# at32f415_soc.net
KiCad netlist of a schematic drawn in Altium Designer
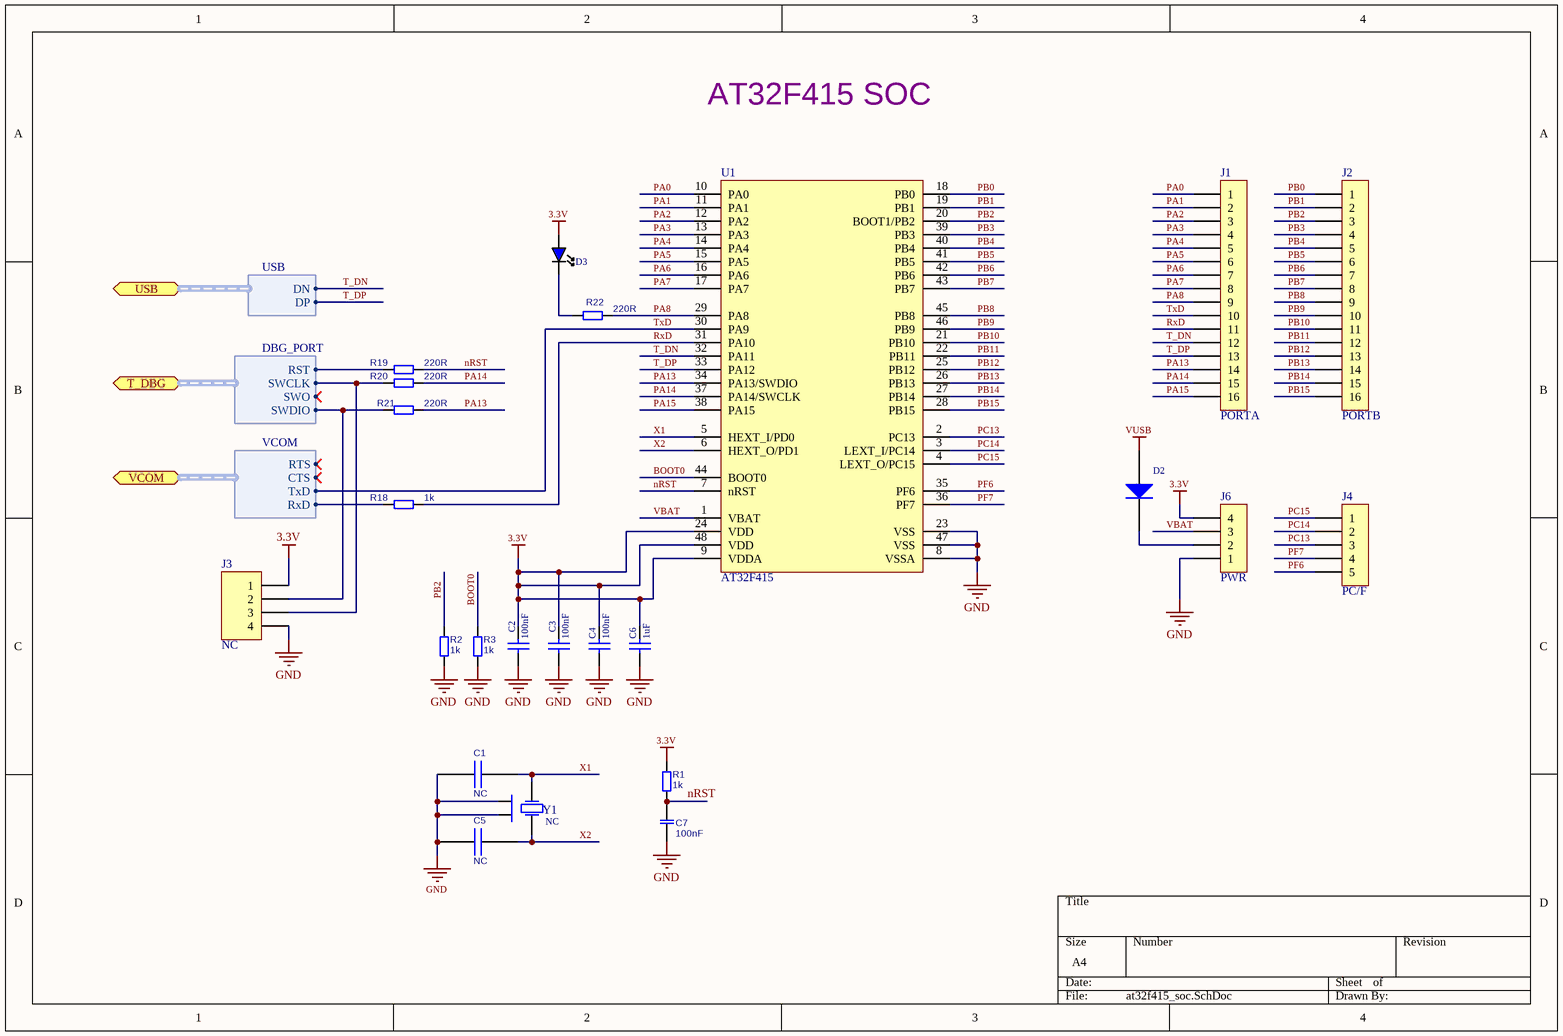
[diagram p0: at32f415_soc.SchDoc]

(export (version "E")
  (design (tool "Eeschema 10.0.6"))
  (components
    (comp (ref "C1")
      (value "NC")
      (footprint "C0402")
      (description "Ceramic Capacitor")
      (libsource (lib "hdesign") (part "Cap1"))
    )
    (comp (ref "C2")
      (value "100nF")
      (footprint "C0402")
      (description "Capacitor")
      (fields (field (name "PUBLISHER") "Altium Limited"))
      (libsource (lib "Miscellaneous Devices") (part "Cap"))
    )
    (comp (ref "C3")
      (value "100nF")
      (footprint "C0402")
      (description "Capacitor")
      (fields (field (name "PUBLISHER") "Altium Limited"))
      (libsource (lib "Miscellaneous Devices") (part "Cap"))
    )
    (comp (ref "C4")
      (value "100nF")
      (footprint "C0402")
      (description "Capacitor")
      (fields (field (name "PUBLISHER") "Altium Limited"))
      (libsource (lib "Miscellaneous Devices") (part "Cap"))
    )
    (comp (ref "C5")
      (value "NC")
      (footprint "C0402")
      (description "Ceramic Capacitor")
      (libsource (lib "hdesign") (part "Cap1"))
    )
    (comp (ref "C6")
      (value "1uF")
      (footprint "C0603")
      (description "Capacitor")
      (fields (field (name "PUBLISHER") "Altium Limited"))
      (libsource (lib "Miscellaneous Devices") (part "Cap"))
    )
    (comp (ref "C7")
      (value "100nF")
      (footprint "C0402")
      (description "Ceramic Capacitor")
      (libsource (lib "hdesign") (part "Cap"))
    )
    (comp (ref "D2")
      (value "Diode")
      (footprint "SOD123")
      (description "Generic Diode")
      (libsource (lib "hdesign") (part "Diode"))
    )
    (comp (ref "D3")
      (value "User LED")
      (footprint "LED0603")
      (description "Green LED")
      (fields (field (name "PART NUMBER") "150060VS75020"))
      (libsource (lib "hdesign") (part "LED_BLUE"))
    )
    (comp (ref "J1")
      (value "PORTA")
      (footprint "HDR1X16")
      (description "100mil, 1x16 header")
      (libsource (lib "at32f415") (part "HEADER1x16"))
    )
    (comp (ref "J2")
      (value "PORTB")
      (footprint "HDR1X16")
      (description "100mil, 1x16 header")
      (libsource (lib "at32f415") (part "HEADER1x16"))
    )
    (comp (ref "J3")
      (value "NC")
      (footprint "HDR1X4")
      (description "Header, 4-Pin")
      (libsource (lib "Miscellaneous Connectors") (part "Header 4"))
    )
    (comp (ref "J4")
      (value "PC/F")
      (footprint "HDR1X5")
      (description "100mil, 1x5 header")
      (libsource (lib "at32f415") (part "HEADER1X5"))
    )
    (comp (ref "J6")
      (value "PWR")
      (footprint "HDR1X4")
      (description "100mil, 1x4 header")
      (libsource (lib "at32f415") (part "HEADER1X4"))
    )
    (comp (ref "R1")
      (value "1k")
      (footprint "R0402")
      (description "Resistor")
      (libsource (lib "hdesign") (part "Res"))
    )
    (comp (ref "R2")
      (value "1k")
      (footprint "R0402")
      (description "Resistor")
      (libsource (lib "hdesign") (part "Res"))
    )
    (comp (ref "R3")
      (value "1k")
      (footprint "R0402")
      (description "Resistor")
      (libsource (lib "hdesign") (part "Res"))
    )
    (comp (ref "R18")
      (value "1k")
      (footprint "R0402")
      (description "Resistor")
      (libsource (lib "hdesign") (part "Res"))
    )
    (comp (ref "R19")
      (value "220R")
      (footprint "R0402")
      (description "Resistor")
      (libsource (lib "hdesign") (part "Res"))
    )
    (comp (ref "R20")
      (value "220R")
      (footprint "R0402")
      (description "Resistor")
      (libsource (lib "hdesign") (part "Res"))
    )
    (comp (ref "R21")
      (value "220R")
      (footprint "R0402")
      (description "Resistor")
      (libsource (lib "hdesign") (part "Res"))
    )
    (comp (ref "R22")
      (value "220R")
      (footprint "R0402")
      (description "Resistor")
      (libsource (lib "hdesign") (part "Res"))
    )
    (comp (ref "U1")
      (value "AT32F415")
      (footprint "LQFP48_M")
      (description "Cortex-M4 MCU")
      (libsource (lib "at32f415") (part "AT32F415"))
    )
    (comp (ref "Y1")
      (value "NC")
      (footprint "XTAL_3225")
      (description "12Mhz CERAMIC SMD CRYSTAL")
      (libsource (lib "hdesign") (part "XTAL_4_PIN"))
    )
  )
  (nets
    (net (code "4") (name "/BOOT0") (class "Default")
      (node (ref "R3") (pin "1") (pinfunction "K_1") (pintype "passive"))
      (node (ref "U1") (pin "44") (pinfunction "BOOT0_44") (pintype "passive"))
    )
    (net (code "5") (name "/PA0") (class "Default")
      (node (ref "J1") (pin "1") (pinfunction "1_1") (pintype "passive"))
      (node (ref "U1") (pin "10") (pinfunction "PA0_10") (pintype "passive"))
    )
    (net (code "6") (name "/PA1") (class "Default")
      (node (ref "J1") (pin "2") (pinfunction "2_2") (pintype "passive"))
      (node (ref "U1") (pin "11") (pinfunction "PA1_11") (pintype "passive"))
    )
    (net (code "7") (name "/PA2") (class "Default")
      (node (ref "J1") (pin "3") (pinfunction "3_3") (pintype "passive"))
      (node (ref "U1") (pin "12") (pinfunction "PA2_12") (pintype "passive"))
    )
    (net (code "8") (name "/PA3") (class "Default")
      (node (ref "J1") (pin "4") (pinfunction "4_4") (pintype "passive"))
      (node (ref "U1") (pin "13") (pinfunction "PA3_13") (pintype "passive"))
    )
    (net (code "9") (name "/PA4") (class "Default")
      (node (ref "J1") (pin "5") (pinfunction "5_5") (pintype "passive"))
      (node (ref "U1") (pin "14") (pinfunction "PA4_14") (pintype "passive"))
    )
    (net (code "10") (name "/PA5") (class "Default")
      (node (ref "J1") (pin "6") (pinfunction "6_6") (pintype "passive"))
      (node (ref "U1") (pin "15") (pinfunction "PA5_15") (pintype "passive"))
    )
    (net (code "11") (name "/PA6") (class "Default")
      (node (ref "J1") (pin "7") (pinfunction "7_7") (pintype "passive"))
      (node (ref "U1") (pin "16") (pinfunction "PA6_16") (pintype "passive"))
    )
    (net (code "12") (name "/PA7") (class "Default")
      (node (ref "J1") (pin "8") (pinfunction "8_8") (pintype "passive"))
      (node (ref "U1") (pin "17") (pinfunction "PA7_17") (pintype "passive"))
    )
    (net (code "13") (name "/PA8") (class "Default")
      (node (ref "J1") (pin "9") (pinfunction "9_9") (pintype "passive"))
      (node (ref "R22") (pin "1") (pinfunction "K_1") (pintype "passive"))
      (node (ref "U1") (pin "29") (pinfunction "PA8_29") (pintype "passive"))
    )
    (net (code "14") (name "/PA13") (class "Default")
      (node (ref "J1") (pin "14") (pinfunction "14_14") (pintype "passive"))
      (node (ref "R21") (pin "1") (pinfunction "K_1") (pintype "passive"))
      (node (ref "U1") (pin "34") (pinfunction "PA13/SWDIO_34") (pintype "passive"))
    )
    (net (code "15") (name "/PA14") (class "Default")
      (node (ref "J1") (pin "15") (pinfunction "15_15") (pintype "passive"))
      (node (ref "R20") (pin "1") (pinfunction "K_1") (pintype "passive"))
      (node (ref "U1") (pin "37") (pinfunction "PA14/SWCLK_37") (pintype "passive"))
    )
    (net (code "16") (name "/PA15") (class "Default")
      (node (ref "J1") (pin "16") (pinfunction "16_16") (pintype "passive"))
      (node (ref "U1") (pin "38") (pinfunction "PA15_38") (pintype "passive"))
    )
    (net (code "17") (name "/PB0") (class "Default")
      (node (ref "J2") (pin "1") (pinfunction "1_1") (pintype "passive"))
      (node (ref "U1") (pin "18") (pinfunction "PB0_18") (pintype "passive"))
    )
    (net (code "18") (name "/PB1") (class "Default")
      (node (ref "J2") (pin "2") (pinfunction "2_2") (pintype "passive"))
      (node (ref "U1") (pin "19") (pinfunction "PB1_19") (pintype "passive"))
    )
    (net (code "19") (name "/PB2") (class "Default")
      (node (ref "J2") (pin "3") (pinfunction "3_3") (pintype "passive"))
      (node (ref "R2") (pin "2") (pinfunction "A_2") (pintype "passive"))
      (node (ref "U1") (pin "20") (pinfunction "BOOT1/PB2_20") (pintype "passive"))
    )
    (net (code "20") (name "/PB3") (class "Default")
      (node (ref "J2") (pin "4") (pinfunction "4_4") (pintype "passive"))
      (node (ref "U1") (pin "39") (pinfunction "PB3_39") (pintype "passive"))
    )
    (net (code "21") (name "/PB4") (class "Default")
      (node (ref "J2") (pin "5") (pinfunction "5_5") (pintype "passive"))
      (node (ref "U1") (pin "40") (pinfunction "PB4_40") (pintype "passive"))
    )
    (net (code "22") (name "/PB5") (class "Default")
      (node (ref "J2") (pin "6") (pinfunction "6_6") (pintype "passive"))
      (node (ref "U1") (pin "41") (pinfunction "PB5_41") (pintype "passive"))
    )
    (net (code "23") (name "/PB6") (class "Default")
      (node (ref "J2") (pin "7") (pinfunction "7_7") (pintype "passive"))
      (node (ref "U1") (pin "42") (pinfunction "PB6_42") (pintype "passive"))
    )
    (net (code "24") (name "/PB7") (class "Default")
      (node (ref "J2") (pin "8") (pinfunction "8_8") (pintype "passive"))
      (node (ref "U1") (pin "43") (pinfunction "PB7_43") (pintype "passive"))
    )
    (net (code "25") (name "/PB8") (class "Default")
      (node (ref "J2") (pin "9") (pinfunction "9_9") (pintype "passive"))
      (node (ref "U1") (pin "45") (pinfunction "PB8_45") (pintype "passive"))
    )
    (net (code "26") (name "/PB9") (class "Default")
      (node (ref "J2") (pin "10") (pinfunction "10_10") (pintype "passive"))
      (node (ref "U1") (pin "46") (pinfunction "PB9_46") (pintype "passive"))
    )
    (net (code "27") (name "/PB10") (class "Default")
      (node (ref "J2") (pin "11") (pinfunction "11_11") (pintype "passive"))
      (node (ref "U1") (pin "21") (pinfunction "PB10_21") (pintype "passive"))
    )
    (net (code "28") (name "/PB11") (class "Default")
      (node (ref "J2") (pin "12") (pinfunction "12_12") (pintype "passive"))
      (node (ref "U1") (pin "22") (pinfunction "PB11_22") (pintype "passive"))
    )
    (net (code "29") (name "/PB12") (class "Default")
      (node (ref "J2") (pin "13") (pinfunction "13_13") (pintype "passive"))
      (node (ref "U1") (pin "25") (pinfunction "PB12_25") (pintype "passive"))
    )
    (net (code "30") (name "/PB13") (class "Default")
      (node (ref "J2") (pin "14") (pinfunction "14_14") (pintype "passive"))
      (node (ref "U1") (pin "26") (pinfunction "PB13_26") (pintype "passive"))
    )
    (net (code "31") (name "/PB14") (class "Default")
      (node (ref "J2") (pin "15") (pinfunction "15_15") (pintype "passive"))
      (node (ref "U1") (pin "27") (pinfunction "PB14_27") (pintype "passive"))
    )
    (net (code "32") (name "/PB15") (class "Default")
      (node (ref "J2") (pin "16") (pinfunction "16_16") (pintype "passive"))
      (node (ref "U1") (pin "28") (pinfunction "PB15_28") (pintype "passive"))
    )
    (net (code "33") (name "/PC13") (class "Default")
      (node (ref "J4") (pin "3") (pinfunction "3_3") (pintype "passive"))
      (node (ref "U1") (pin "2") (pinfunction "PC13_2") (pintype "passive"))
    )
    (net (code "34") (name "/PC14") (class "Default")
      (node (ref "J4") (pin "2") (pinfunction "2_2") (pintype "passive"))
      (node (ref "U1") (pin "3") (pinfunction "LEXT_I/PC14_3") (pintype "passive"))
    )
    (net (code "35") (name "/PC15") (class "Default")
      (node (ref "J4") (pin "1") (pinfunction "1_1") (pintype "passive"))
      (node (ref "U1") (pin "4") (pinfunction "LEXT_O/PC15_4") (pintype "passive"))
    )
    (net (code "36") (name "/PF6") (class "Default")
      (node (ref "J4") (pin "5") (pinfunction "5_5") (pintype "passive"))
      (node (ref "U1") (pin "35") (pinfunction "PF6_35") (pintype "passive"))
    )
    (net (code "37") (name "/PF7") (class "Default")
      (node (ref "J4") (pin "4") (pinfunction "4_4") (pintype "passive"))
      (node (ref "U1") (pin "36") (pinfunction "PF7_36") (pintype "passive"))
    )
    (net (code "38") (name "/RST") (class "Default")
      (node (ref "R19") (pin "2") (pinfunction "A_2") (pintype "passive"))
    )
    (net (code "39") (name "/RxD") (class "Default")
      (node (ref "J1") (pin "11") (pinfunction "11_11") (pintype "passive"))
      (node (ref "R18") (pin "2") (pinfunction "A_2") (pintype "passive"))
      (node (ref "U1") (pin "31") (pinfunction "PA10_31") (pintype "passive"))
    )
    (net (code "40") (name "/SWCLK") (class "Default")
      (node (ref "J3") (pin "3") (pinfunction "3_3") (pintype "passive"))
      (node (ref "R20") (pin "2") (pinfunction "A_2") (pintype "passive"))
    )
    (net (code "41") (name "/SWDIO") (class "Default")
      (node (ref "J3") (pin "2") (pinfunction "2_2") (pintype "passive"))
      (node (ref "R21") (pin "2") (pinfunction "A_2") (pintype "passive"))
    )
    (net (code "42") (name "/T_DN") (class "Default")
      (node (ref "J1") (pin "12") (pinfunction "12_12") (pintype "passive"))
      (node (ref "U1") (pin "32") (pinfunction "PA11_32") (pintype "passive"))
    )
    (net (code "43") (name "/T_DP") (class "Default")
      (node (ref "J1") (pin "13") (pinfunction "13_13") (pintype "passive"))
      (node (ref "U1") (pin "33") (pinfunction "PA12_33") (pintype "passive"))
    )
    (net (code "44") (name "/TxD") (class "Default")
      (node (ref "J1") (pin "10") (pinfunction "10_10") (pintype "passive"))
      (node (ref "U1") (pin "30") (pinfunction "PA9_30") (pintype "passive"))
    )
    (net (code "45") (name "/VBAT") (class "Default")
      (node (ref "J6") (pin "3") (pinfunction "3_3") (pintype "passive"))
      (node (ref "U1") (pin "1") (pinfunction "VBAT_1") (pintype "passive"))
    )
    (net (code "46") (name "/X1") (class "Default")
      (node (ref "C1") (pin "2") (pinfunction "N_2") (pintype "passive"))
      (node (ref "U1") (pin "5") (pinfunction "HEXT_I/PD0_5") (pintype "passive"))
      (node (ref "Y1") (pin "1") (pinfunction "X1_1") (pintype "passive"))
    )
    (net (code "47") (name "/X2") (class "Default")
      (node (ref "C5") (pin "2") (pinfunction "N_2") (pintype "passive"))
      (node (ref "U1") (pin "6") (pinfunction "HEXT_O/PD1_6") (pintype "passive"))
      (node (ref "Y1") (pin "3") (pinfunction "X2_3") (pintype "passive"))
    )
    (net (code "48") (name "/nRST") (class "Default")
      (node (ref "C7") (pin "2") (pinfunction "A_2") (pintype "passive"))
      (node (ref "R1") (pin "2") (pinfunction "A_2") (pintype "passive"))
      (node (ref "R19") (pin "1") (pinfunction "K_1") (pintype "passive"))
      (node (ref "U1") (pin "7") (pinfunction "nRST_7") (pintype "passive"))
    )
    (net (code "52") (name "3.3V") (class "Default")
      (node (ref "C2") (pin "1") (pinfunction "1_1") (pintype "passive"))
      (node (ref "C3") (pin "1") (pinfunction "1_1") (pintype "passive"))
      (node (ref "C4") (pin "1") (pinfunction "1_1") (pintype "passive"))
      (node (ref "C6") (pin "1") (pinfunction "1_1") (pintype "passive"))
      (node (ref "D3") (pin "A") (pinfunction "A_A") (pintype "passive"))
      (node (ref "J3") (pin "1") (pinfunction "1_1") (pintype "passive"))
      (node (ref "J6") (pin "4") (pinfunction "4_4") (pintype "passive"))
      (node (ref "R1") (pin "1") (pinfunction "K_1") (pintype "passive"))
      (node (ref "U1") (pin "24") (pinfunction "VDD_24") (pintype "passive"))
      (node (ref "U1") (pin "48") (pinfunction "VDD_48") (pintype "passive"))
      (node (ref "U1") (pin "9") (pinfunction "VDDA_9") (pintype "passive"))
    )
    (net (code "53") (name "GND") (class "Default")
      (node (ref "C1") (pin "1") (pinfunction "P_1") (pintype "passive"))
      (node (ref "C2") (pin "2") (pinfunction "2_2") (pintype "passive"))
      (node (ref "C3") (pin "2") (pinfunction "2_2") (pintype "passive"))
      (node (ref "C4") (pin "2") (pinfunction "2_2") (pintype "passive"))
      (node (ref "C5") (pin "1") (pinfunction "P_1") (pintype "passive"))
      (node (ref "C6") (pin "2") (pinfunction "2_2") (pintype "passive"))
      (node (ref "C7") (pin "1") (pinfunction "K_1") (pintype "passive"))
      (node (ref "J3") (pin "4") (pinfunction "4_4") (pintype "passive"))
      (node (ref "J6") (pin "1") (pinfunction "1_1") (pintype "passive"))
      (node (ref "R2") (pin "1") (pinfunction "K_1") (pintype "passive"))
      (node (ref "R3") (pin "2") (pinfunction "A_2") (pintype "passive"))
      (node (ref "U1") (pin "23") (pinfunction "VSS_23") (pintype "passive"))
      (node (ref "U1") (pin "47") (pinfunction "VSS_47") (pintype "passive"))
      (node (ref "U1") (pin "8") (pinfunction "VSSA_8") (pintype "passive"))
      (node (ref "Y1") (pin "2") (pinfunction "2_2") (pintype "passive"))
      (node (ref "Y1") (pin "4") (pinfunction "X2_4") (pintype "passive"))
    )
    (net (code "54") (name "Net-(D2-PadK)") (class "Default")
      (node (ref "D2") (pin "K") (pinfunction "K_K") (pintype "passive"))
      (node (ref "J6") (pin "2") (pinfunction "2_2") (pintype "passive"))
    )
    (net (code "55") (name "Net-(R22-A)") (class "Default")
      (node (ref "D3") (pin "k") (pinfunction "k_k") (pintype "passive"))
      (node (ref "R22") (pin "2") (pinfunction "A_2") (pintype "passive"))
    )
    (net (code "56") (name "VUSB") (class "Default")
      (node (ref "D2") (pin "A") (pinfunction "A_A") (pintype "passive"))
    )
    (net (code "57") (name "unconnected-(R18-K-Pad1)") (class "Default")
      (node (ref "R18") (pin "1") (pinfunction "K_1") (pintype "passive"))
    )
  )
)
